# Shem_1.net
KiCad netlist of a schematic drawn in Altium Designer
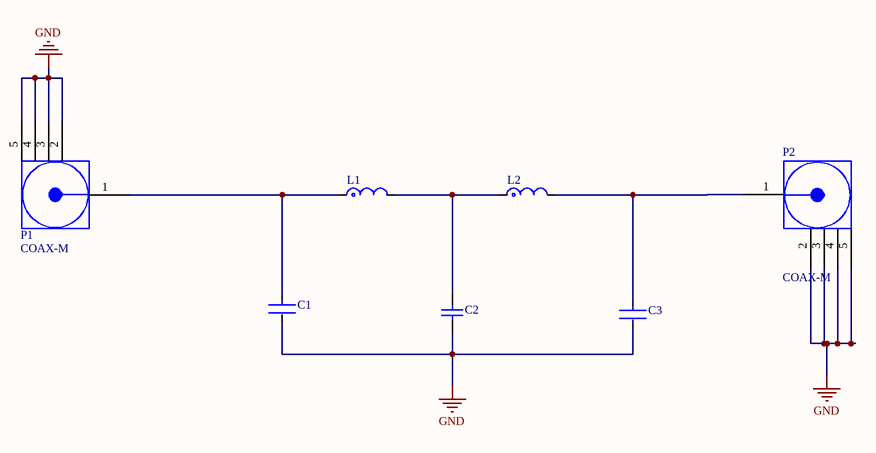
[diagram p0: Shem_1.SchDoc]

(export (version "E")
  (design (tool "Eeschema 10.0.6"))
  (components
    (comp (ref "C1")
      (value "C0603C180F5GACTU")
      (footprint "FP-C0603C-CF-MFG")
      (description "C0603 18 pF C0G 30ppm/°C 1.00% 50 V")
      (fields
        (field (name "TOLERANCE") "0.01")
        (field (name "OCTOPART") "https://octopart.com/c0603c180f5gactu-kemet-47052343")
      )
      (libsource (lib "Altium Content Vault") (part "b4654b650e69147ec39a6b967a45e02"))
    )
    (comp (ref "C2")
      (value "C0402T330J3GACTU")
      (footprint "CAPC1005X55X30ML05T10")
      (description "±5% 25V Ceramic Capacitor C0G, \r\n33 pF, NP0 0402 (1005 Metric)")
      (fields (field (name "MANUFACTURER") "Kemet"))
      (libsource (lib "Altium Content Vault") (part "CAP"))
    )
    (comp (ref "C3")
      (value "C0603C180F5GACTU")
      (footprint "FP-C0603C-CF-MFG")
      (description "C0603 18 pF C0G 30ppm/°C 1.00% 50 V")
      (fields
        (field (name "TOLERANCE") "0.01")
        (field (name "OCTOPART") "https://octopart.com/c0603c180f5gactu-kemet-47052343")
      )
      (libsource (lib "Altium Content Vault") (part "b4654b650e69147ec39a6b967a45e02"))
    )
    (comp (ref "L1")
      (value "LQG15WZ62NG02D")
      (footprint "FP-LQG15HH_02-MFG")
      (description "Fixed Inductors 0402 62nH 2% 180mA 1.9ohm AEC-Q200")
      (fields (field (name "TOLERANCE") "5%"))
      (libsource (lib "Altium Content Vault") (part "4cc4b267dca4c8e51f7102f422741d8"))
    )
    (comp (ref "L2")
      (value "LQG15WZ62NG02D")
      (footprint "FP-LQG15HH_02-MFG")
      (description "Fixed Inductors 0402 62nH 2% 180mA 1.9ohm AEC-Q200")
      (fields (field (name "TOLERANCE") "5%"))
      (libsource (lib "Altium Content Vault") (part "4cc4b267dca4c8e51f7102f422741d8"))
    )
    (comp (ref "P1")
      (value "COAX-M")
      (footprint "COAX-M")
      (libsource (lib "Integrated_Library1") (part "COAX-M"))
    )
    (comp (ref "P2")
      (value "COAX-M")
      (footprint "COAX-M")
      (libsource (lib "Integrated_Library1") (part "COAX-M"))
    )
  )
  (nets
    (net (code "1") (name "GND") (class "Default")
      (node (ref "C1") (pin "2") (pinfunction "2_2") (pintype "passive"))
      (node (ref "C2") (pin "1") (pinfunction "1_1") (pintype "passive"))
      (node (ref "C3") (pin "2") (pinfunction "2_2") (pintype "passive"))
      (node (ref "P1") (pin "2") (pinfunction "2_2") (pintype "passive"))
      (node (ref "P1") (pin "3") (pinfunction "3_3") (pintype "passive"))
      (node (ref "P1") (pin "4") (pinfunction "4_4") (pintype "passive"))
      (node (ref "P1") (pin "5") (pinfunction "5_5") (pintype "passive"))
      (node (ref "P2") (pin "2") (pinfunction "2_2") (pintype "passive"))
      (node (ref "P2") (pin "3") (pinfunction "3_3") (pintype "passive"))
      (node (ref "P2") (pin "4") (pinfunction "4_4") (pintype "passive"))
      (node (ref "P2") (pin "5") (pinfunction "5_5") (pintype "passive"))
    )
    (net (code "2") (name "Net-(C1-Pad1)") (class "Default")
      (node (ref "C1") (pin "1") (pinfunction "1_1") (pintype "passive"))
      (node (ref "L1") (pin "1") (pinfunction "1_1") (pintype "passive"))
      (node (ref "P1") (pin "1") (pinfunction "1_1") (pintype "passive"))
    )
    (net (code "3") (name "Net-(C2-Pad2)") (class "Default")
      (node (ref "C2") (pin "2") (pinfunction "2_2") (pintype "passive"))
      (node (ref "L1") (pin "2") (pinfunction "2_2") (pintype "passive"))
      (node (ref "L2") (pin "1") (pinfunction "1_1") (pintype "passive"))
    )
    (net (code "4") (name "Net-(C3-Pad1)") (class "Default")
      (node (ref "C3") (pin "1") (pinfunction "1_1") (pintype "passive"))
      (node (ref "L2") (pin "2") (pinfunction "2_2") (pintype "passive"))
      (node (ref "P2") (pin "1") (pinfunction "1_1") (pintype "passive"))
    )
  )
)
